# imxbblcd.net
KiCad netlist of a schematic drawn in Altium Designer
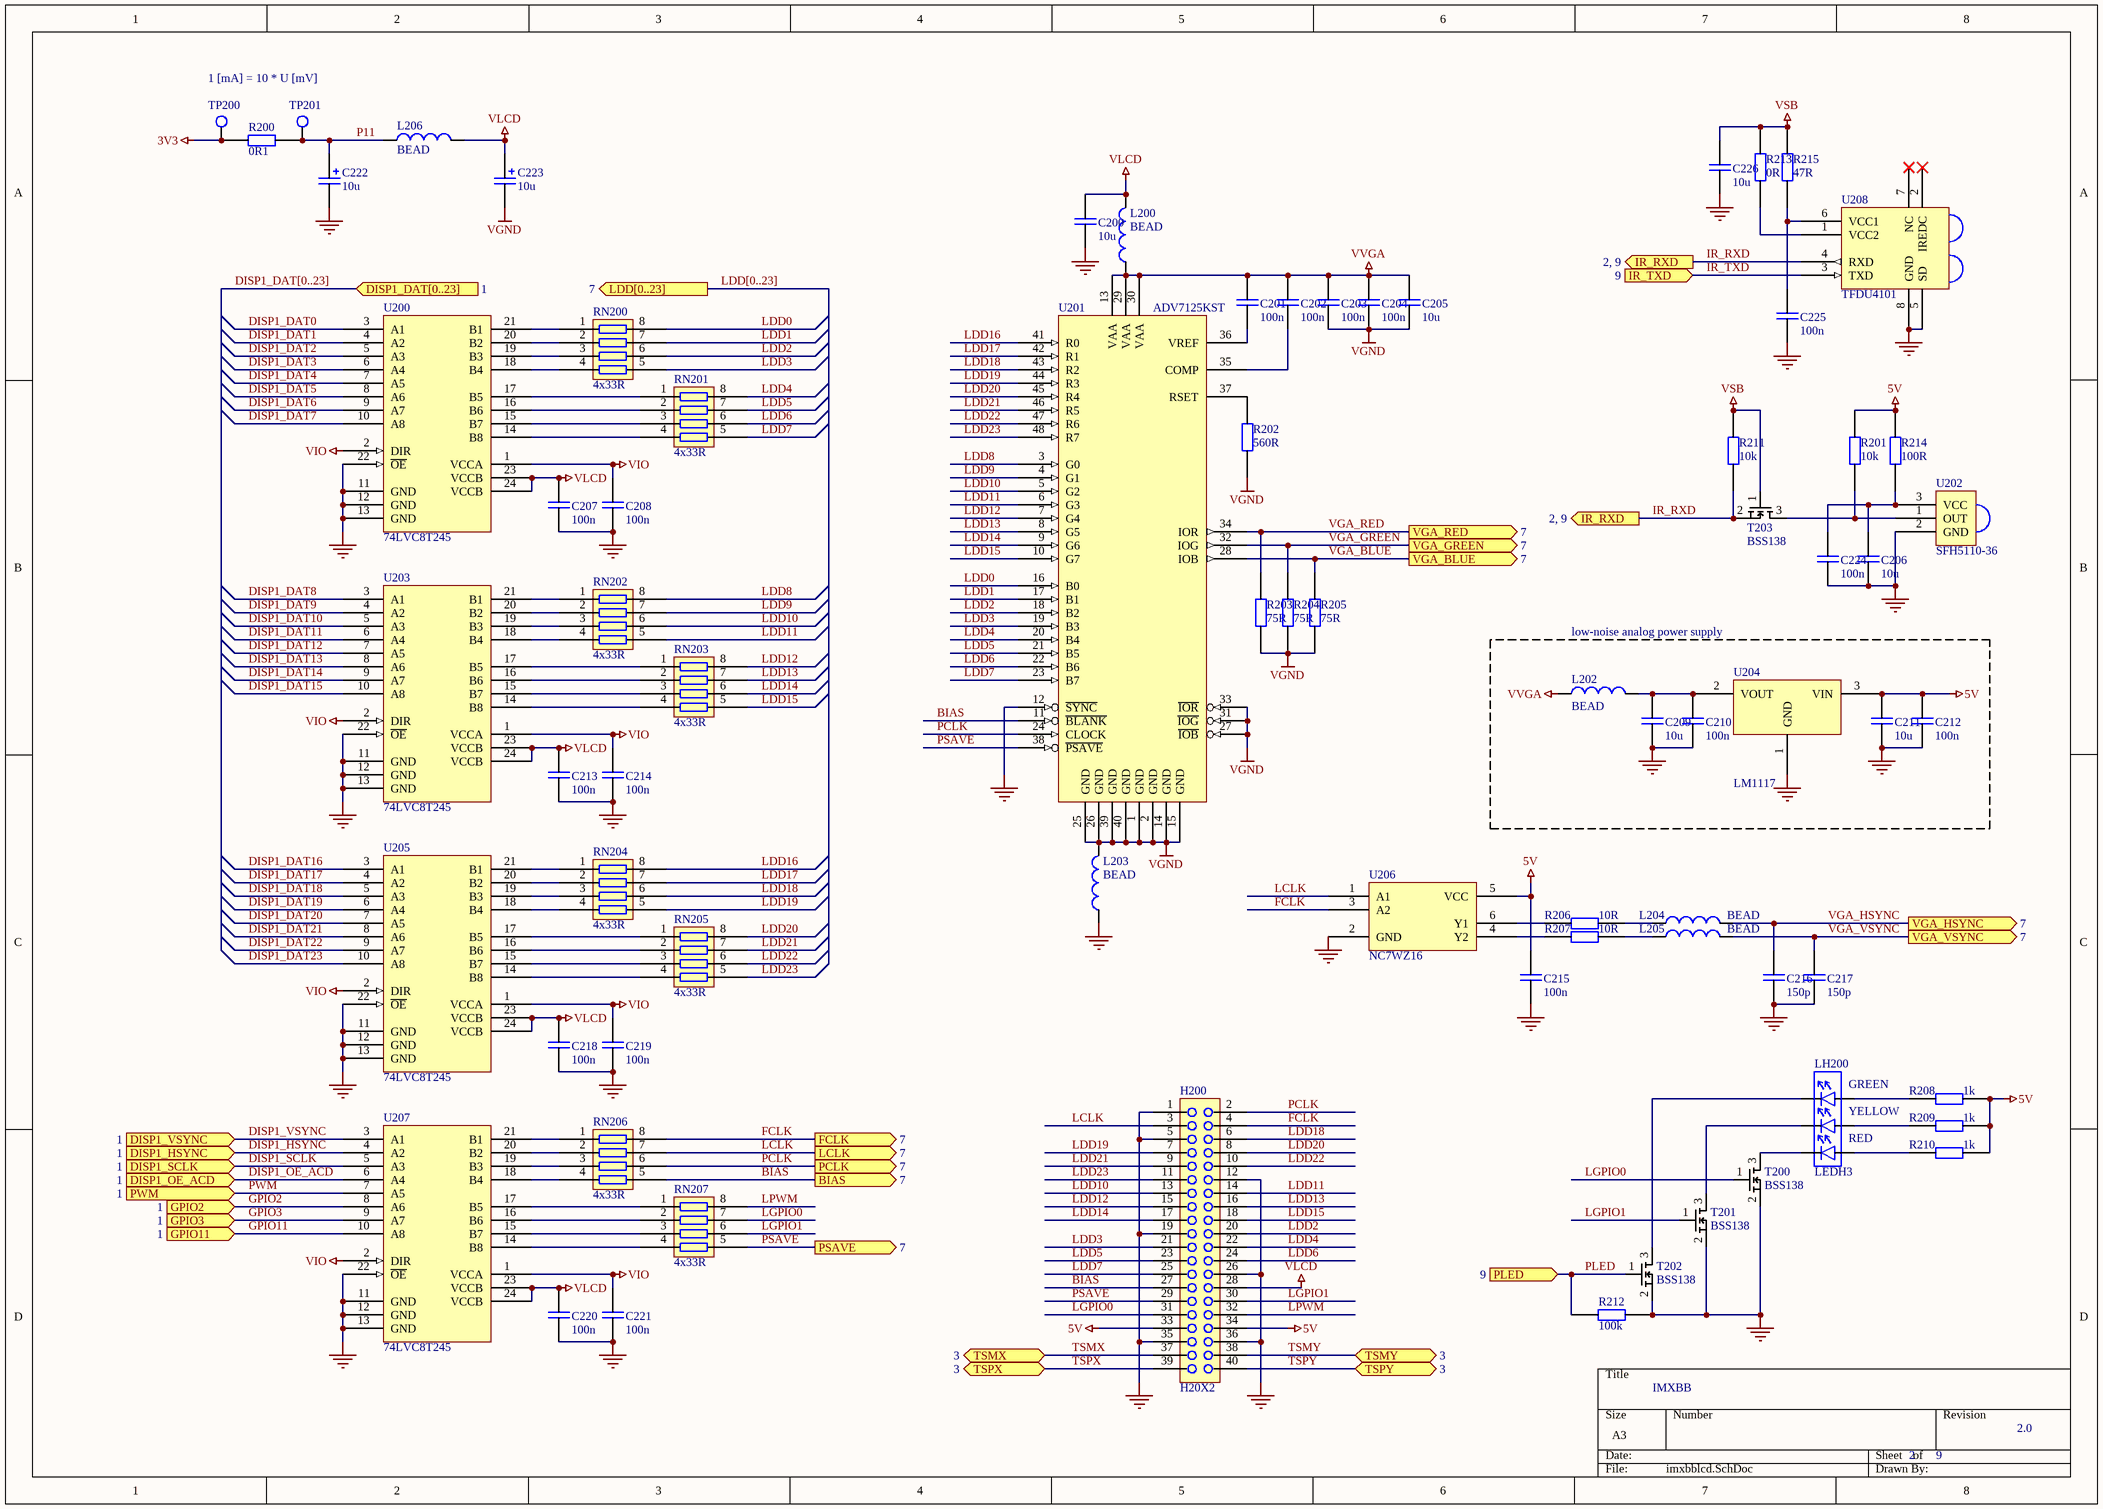
[diagram p0: imxbblcd.SchDoc]

(export (version "E")
  (design (tool "Eeschema 10.0.6"))
  (components
    (comp (ref "C200") (value "10u") (footprint "0805") (libsource (lib "imxbb") (part "C")))
    (comp (ref "C201") (value "100n") (footprint "0603") (libsource (lib "imxbb") (part "C")))
    (comp (ref "C202") (value "100n") (footprint "0603") (libsource (lib "imxbb") (part "C")))
    (comp (ref "C203") (value "100n") (footprint "0603") (libsource (lib "imxbb") (part "C")))
    (comp (ref "C204") (value "100n") (footprint "0603") (libsource (lib "imxbb") (part "C")))
    (comp (ref "C205") (value "10u") (footprint "0805") (libsource (lib "imxbb") (part "C")))
    (comp (ref "C206") (value "10u") (footprint "0805") (libsource (lib "imxbb") (part "C")))
    (comp (ref "C207") (value "100n") (footprint "0603") (libsource (lib "imxbb") (part "C")))
    (comp (ref "C208") (value "100n") (footprint "0603") (libsource (lib "imxbb") (part "C")))
    (comp (ref "C209") (value "10u") (footprint "0805") (libsource (lib "imxbb") (part "C")))
    (comp (ref "C210") (value "100n") (footprint "0603") (libsource (lib "imxbb") (part "C")))
    (comp (ref "C211") (value "10u") (footprint "0805") (libsource (lib "imxbb") (part "C")))
    (comp (ref "C212") (value "100n") (footprint "0603") (libsource (lib "imxbb") (part "C")))
    (comp (ref "C213") (value "100n") (footprint "0603") (libsource (lib "imxbb") (part "C")))
    (comp (ref "C214") (value "100n") (footprint "0603") (libsource (lib "imxbb") (part "C")))
    (comp (ref "C215") (value "100n") (footprint "0603") (libsource (lib "imxbb") (part "C")))
    (comp (ref "C216") (value "150p") (footprint "0603") (libsource (lib "imxbb") (part "C")))
    (comp (ref "C217") (value "150p") (footprint "0603") (libsource (lib "imxbb") (part "C")))
    (comp (ref "C218") (value "100n") (footprint "0603") (libsource (lib "imxbb") (part "C")))
    (comp (ref "C219") (value "100n") (footprint "0603") (libsource (lib "imxbb") (part "C")))
    (comp (ref "C220") (value "100n") (footprint "0603") (libsource (lib "imxbb") (part "C")))
    (comp (ref "C221") (value "100n") (footprint "0603") (libsource (lib "imxbb") (part "C")))
    (comp (ref "C222") (value "10u") (footprint "3216A") (libsource (lib "imxbb") (part "C+")))
    (comp (ref "C223") (value "10u") (footprint "3216A") (libsource (lib "imxbb") (part "C+")))
    (comp (ref "C224") (value "100n") (footprint "0603") (libsource (lib "imxbb") (part "C")))
    (comp (ref "C225") (value "100n") (footprint "0603") (libsource (lib "imxbb") (part "C")))
    (comp (ref "C226") (value "10u") (footprint "0805") (libsource (lib "imxbb") (part "C")))
    (comp (ref "H200") (value "H20X2") (footprint "H2x20") (libsource (lib "imxbb") (part "H20X2")))
    (comp (ref "L200") (value "BEAD") (footprint "0603") (libsource (lib "imxbb") (part "FBEAD")))
    (comp (ref "L202") (value "BEAD") (footprint "0603") (libsource (lib "imxbb") (part "FBEAD")))
    (comp (ref "L203") (value "BEAD") (footprint "0603") (libsource (lib "imxbb") (part "FBEAD")))
    (comp (ref "L204") (value "BEAD") (footprint "0603") (libsource (lib "imxbb") (part "FBEAD")))
    (comp (ref "L205") (value "BEAD") (footprint "0603") (libsource (lib "imxbb") (part "FBEAD")))
    (comp (ref "L206") (value "BEAD") (footprint "0603") (libsource (lib "") (part "FBEAD_1")))
    (comp (ref "LH200") (value "LEDH3") (footprint "LED HOLDER 3") (libsource (lib "imxbb") (part "LEDH3")))
    (comp (ref "R200") (value "0R1") (footprint "0603") (libsource (lib "") (part "R_3")))
    (comp (ref "R201") (value "10k") (footprint "0603") (libsource (lib "") (part "R_2")))
    (comp (ref "R202") (value "560R") (footprint "0603") (libsource (lib "") (part "R_1")))
    (comp (ref "R203") (value "75R") (footprint "0603") (libsource (lib "") (part "R_1")))
    (comp (ref "R204") (value "75R") (footprint "0603") (libsource (lib "") (part "R_1")))
    (comp (ref "R205") (value "75R") (footprint "0603") (libsource (lib "") (part "R_1")))
    (comp (ref "R206") (value "10R") (footprint "0603") (libsource (lib "imxbb") (part "R")))
    (comp (ref "R207") (value "10R") (footprint "0603") (libsource (lib "imxbb") (part "R")))
    (comp (ref "R208") (value "1k") (footprint "0603") (libsource (lib "imxbb") (part "R")))
    (comp (ref "R209") (value "1k") (footprint "0603") (libsource (lib "imxbb") (part "R")))
    (comp (ref "R210") (value "1k") (footprint "0603") (libsource (lib "imxbb") (part "R")))
    (comp (ref "R211") (value "10k") (footprint "0603") (libsource (lib "") (part "R_2")))
    (comp (ref "R212") (value "100k") (footprint "0603") (libsource (lib "") (part "R_3")))
    (comp (ref "R213") (value "0R") (footprint "0603") (libsource (lib "") (part "R_1")))
    (comp (ref "R214") (value "100R") (footprint "0603") (libsource (lib "") (part "R_2")))
    (comp (ref "R215") (value "47R") (footprint "0603") (libsource (lib "") (part "R_2")))
    (comp (ref "RN200") (value "4x33R") (footprint "RX4_NS") (libsource (lib "imxbb") (part "RN4")))
    (comp (ref "RN201") (value "4x33R") (footprint "RX4_NS") (libsource (lib "imxbb") (part "RN4")))
    (comp (ref "RN202") (value "4x33R") (footprint "RX4_NS") (libsource (lib "imxbb") (part "RN4")))
    (comp (ref "RN203") (value "4x33R") (footprint "RX4_NS") (libsource (lib "imxbb") (part "RN4")))
    (comp (ref "RN204") (value "4x33R") (footprint "RX4_NS") (libsource (lib "imxbb") (part "RN4")))
    (comp (ref "RN205") (value "4x33R") (footprint "RX4_NS") (libsource (lib "imxbb") (part "RN4")))
    (comp (ref "RN206") (value "4x33R") (footprint "RX4_NS") (libsource (lib "imxbb") (part "RN4")))
    (comp (ref "RN207") (value "4x33R") (footprint "RX4_NS") (libsource (lib "imxbb") (part "RN4")))
    (comp (ref "T200") (value "BSS138") (footprint "SOT23") (libsource (lib "imxbb") (part "BSS138")))
    (comp (ref "T201") (value "BSS138") (footprint "SOT23") (libsource (lib "imxbb") (part "BSS138")))
    (comp (ref "T202") (value "BSS138") (footprint "SOT23") (libsource (lib "imxbb") (part "BSS138")))
    (comp (ref "T203") (value "BSS138") (footprint "SOT23") (libsource (lib "imxbb") (part "BSS138")))
    (comp (ref "TP200")
      (value "TESTPOINT")
      (footprint "TESTPOINT_2mm")
      (description "Testpoint pad")
      (libsource (lib "imxbb") (part "TESTPOINT"))
    )
    (comp (ref "TP201")
      (value "TESTPOINT")
      (footprint "TESTPOINT_2mm")
      (description "Testpoint pad")
      (libsource (lib "imxbb") (part "TESTPOINT"))
    )
    (comp (ref "U200")
      (value "74LVC8T245")
      (footprint "TSSOP24")
      (libsource (lib "imxbb") (part "74LVC8T245"))
    )
    (comp (ref "U201") (value "ADV7125KST") (footprint "LQFP48") (libsource (lib "imxbb") (part "ADV7125")))
    (comp (ref "U202") (value "SFH5110-36") (footprint "SFH511x") (libsource (lib "imxbb") (part "SFH5110")))
    (comp (ref "U203")
      (value "74LVC8T245")
      (footprint "TSSOP24")
      (libsource (lib "imxbb") (part "74LVC8T245"))
    )
    (comp (ref "U204") (value "LM1117") (footprint "SOT223") (libsource (lib "imxbb") (part "LM1117")))
    (comp (ref "U205")
      (value "74LVC8T245")
      (footprint "TSSOP24")
      (libsource (lib "imxbb") (part "74LVC8T245"))
    )
    (comp (ref "U206") (value "NC7WZ16") (footprint "SC70") (libsource (lib "imxbb") (part "NC7WZ16")))
    (comp (ref "U207")
      (value "74LVC8T245")
      (footprint "TSSOP24")
      (libsource (lib "imxbb") (part "74LVC8T245"))
    )
    (comp (ref "U208") (value "TFDU4101") (footprint "TDFU4101") (libsource (lib "imxbb") (part "TFDU4101")))
  )
  (nets
    (net (code "1") (name "/BIAS") (class "Default")
      (node (ref "H200") (pin "27") (pinfunction "27_27") (pintype "passive"))
      (node (ref "RN206") (pin "5") (pintype "passive"))
      (node (ref "U201") (pin "11") (pinfunction "~{BLANK}_11") (pintype "input"))
    )
    (net (code "2") (name "/DISP1_DAT0") (class "Default")
      (node (ref "U200") (pin "3") (pinfunction "A1_3") (pintype "passive"))
    )
    (net (code "3") (name "/DISP1_DAT1") (class "Default")
      (node (ref "U200") (pin "4") (pinfunction "A2_4") (pintype "passive"))
    )
    (net (code "4") (name "/DISP1_DAT2") (class "Default")
      (node (ref "U200") (pin "5") (pinfunction "A3_5") (pintype "passive"))
    )
    (net (code "5") (name "/DISP1_DAT3") (class "Default")
      (node (ref "U200") (pin "6") (pinfunction "A4_6") (pintype "passive"))
    )
    (net (code "6") (name "/DISP1_DAT4") (class "Default")
      (node (ref "U200") (pin "7") (pinfunction "A5_7") (pintype "passive"))
    )
    (net (code "7") (name "/DISP1_DAT5") (class "Default")
      (node (ref "U200") (pin "8") (pinfunction "A6_8") (pintype "passive"))
    )
    (net (code "8") (name "/DISP1_DAT6") (class "Default")
      (node (ref "U200") (pin "9") (pinfunction "A7_9") (pintype "passive"))
    )
    (net (code "9") (name "/DISP1_DAT7") (class "Default")
      (node (ref "U200") (pin "10") (pinfunction "A8_10") (pintype "passive"))
    )
    (net (code "10") (name "/DISP1_DAT8") (class "Default")
      (node (ref "U203") (pin "3") (pinfunction "A1_3") (pintype "passive"))
    )
    (net (code "11") (name "/DISP1_DAT9") (class "Default")
      (node (ref "U203") (pin "4") (pinfunction "A2_4") (pintype "passive"))
    )
    (net (code "12") (name "/DISP1_DAT10") (class "Default")
      (node (ref "U203") (pin "5") (pinfunction "A3_5") (pintype "passive"))
    )
    (net (code "13") (name "/DISP1_DAT11") (class "Default")
      (node (ref "U203") (pin "6") (pinfunction "A4_6") (pintype "passive"))
    )
    (net (code "14") (name "/DISP1_DAT12") (class "Default")
      (node (ref "U203") (pin "7") (pinfunction "A5_7") (pintype "passive"))
    )
    (net (code "15") (name "/DISP1_DAT13") (class "Default")
      (node (ref "U203") (pin "8") (pinfunction "A6_8") (pintype "passive"))
    )
    (net (code "16") (name "/DISP1_DAT14") (class "Default")
      (node (ref "U203") (pin "9") (pinfunction "A7_9") (pintype "passive"))
    )
    (net (code "17") (name "/DISP1_DAT15") (class "Default")
      (node (ref "U203") (pin "10") (pinfunction "A8_10") (pintype "passive"))
    )
    (net (code "18") (name "/DISP1_DAT16") (class "Default")
      (node (ref "U205") (pin "3") (pinfunction "A1_3") (pintype "passive"))
    )
    (net (code "19") (name "/DISP1_DAT17") (class "Default")
      (node (ref "U205") (pin "4") (pinfunction "A2_4") (pintype "passive"))
    )
    (net (code "20") (name "/DISP1_DAT18") (class "Default")
      (node (ref "U205") (pin "5") (pinfunction "A3_5") (pintype "passive"))
    )
    (net (code "21") (name "/DISP1_DAT19") (class "Default")
      (node (ref "U205") (pin "6") (pinfunction "A4_6") (pintype "passive"))
    )
    (net (code "22") (name "/DISP1_DAT20") (class "Default")
      (node (ref "U205") (pin "7") (pinfunction "A5_7") (pintype "passive"))
    )
    (net (code "23") (name "/DISP1_DAT21") (class "Default")
      (node (ref "U205") (pin "8") (pinfunction "A6_8") (pintype "passive"))
    )
    (net (code "24") (name "/DISP1_DAT22") (class "Default")
      (node (ref "U205") (pin "9") (pinfunction "A7_9") (pintype "passive"))
    )
    (net (code "25") (name "/DISP1_DAT23") (class "Default")
      (node (ref "U205") (pin "10") (pinfunction "A8_10") (pintype "passive"))
    )
    (net (code "27") (name "/DISP1_HSYNC") (class "Default")
      (node (ref "U207") (pin "4") (pinfunction "A2_4") (pintype "passive"))
    )
    (net (code "28") (name "/DISP1_OE_ACD") (class "Default")
      (node (ref "U207") (pin "6") (pinfunction "A4_6") (pintype "passive"))
    )
    (net (code "29") (name "/DISP1_SCLK") (class "Default")
      (node (ref "U207") (pin "5") (pinfunction "A3_5") (pintype "passive"))
    )
    (net (code "30") (name "/DISP1_VSYNC") (class "Default")
      (node (ref "U207") (pin "3") (pinfunction "A1_3") (pintype "passive"))
    )
    (net (code "31") (name "/FCLK") (class "Default")
      (node (ref "H200") (pin "4") (pinfunction "4_4") (pintype "passive"))
      (node (ref "RN206") (pin "8") (pintype "passive"))
      (node (ref "U206") (pin "3") (pinfunction "A2_3") (pintype "passive"))
    )
    (net (code "32") (name "/GPIO2") (class "Default")
      (node (ref "U207") (pin "8") (pinfunction "A6_8") (pintype "passive"))
    )
    (net (code "33") (name "/GPIO3") (class "Default")
      (node (ref "U207") (pin "9") (pinfunction "A7_9") (pintype "passive"))
    )
    (net (code "34") (name "/GPIO11") (class "Default")
      (node (ref "U207") (pin "10") (pinfunction "A8_10") (pintype "passive"))
    )
    (net (code "35") (name "/IR_RXD") (class "Default")
      (node (ref "R211") (pin "2") (pinfunction "2_2") (pintype "passive"))
      (node (ref "T203") (pin "2") (pinfunction "S_2") (pintype "passive"))
      (node (ref "U208") (pin "4") (pinfunction "RXD_4") (pintype "output"))
    )
    (net (code "36") (name "/IR_TXD") (class "Default")
      (node (ref "U208") (pin "3") (pinfunction "TXD_3") (pintype "input"))
    )
    (net (code "37") (name "/LCLK") (class "Default")
      (node (ref "H200") (pin "3") (pinfunction "3_3") (pintype "passive"))
      (node (ref "RN206") (pin "7") (pintype "passive"))
      (node (ref "U206") (pin "1") (pinfunction "A1_1") (pintype "passive"))
    )
    (net (code "38") (name "/LDD0") (class "Default")
      (node (ref "RN200") (pin "8") (pintype "passive"))
      (node (ref "U201") (pin "16") (pinfunction "B0_16") (pintype "input"))
    )
    (net (code "39") (name "/LDD1") (class "Default")
      (node (ref "RN200") (pin "7") (pintype "passive"))
      (node (ref "U201") (pin "17") (pinfunction "B1_17") (pintype "input"))
    )
    (net (code "40") (name "/LDD2") (class "Default")
      (node (ref "H200") (pin "20") (pinfunction "20_20") (pintype "passive"))
      (node (ref "RN200") (pin "6") (pintype "passive"))
      (node (ref "U201") (pin "18") (pinfunction "B2_18") (pintype "input"))
    )
    (net (code "41") (name "/LDD3") (class "Default")
      (node (ref "H200") (pin "21") (pinfunction "21_21") (pintype "passive"))
      (node (ref "RN200") (pin "5") (pintype "passive"))
      (node (ref "U201") (pin "19") (pinfunction "B3_19") (pintype "input"))
    )
    (net (code "42") (name "/LDD4") (class "Default")
      (node (ref "H200") (pin "22") (pinfunction "22_22") (pintype "passive"))
      (node (ref "RN201") (pin "8") (pintype "passive"))
      (node (ref "U201") (pin "20") (pinfunction "B4_20") (pintype "input"))
    )
    (net (code "43") (name "/LDD5") (class "Default")
      (node (ref "H200") (pin "23") (pinfunction "23_23") (pintype "passive"))
      (node (ref "RN201") (pin "7") (pintype "passive"))
      (node (ref "U201") (pin "21") (pinfunction "B5_21") (pintype "input"))
    )
    (net (code "44") (name "/LDD6") (class "Default")
      (node (ref "H200") (pin "24") (pinfunction "24_24") (pintype "passive"))
      (node (ref "RN201") (pin "6") (pintype "passive"))
      (node (ref "U201") (pin "22") (pinfunction "B6_22") (pintype "input"))
    )
    (net (code "45") (name "/LDD7") (class "Default")
      (node (ref "H200") (pin "25") (pinfunction "25_25") (pintype "passive"))
      (node (ref "RN201") (pin "5") (pintype "passive"))
      (node (ref "U201") (pin "23") (pinfunction "B7_23") (pintype "input"))
    )
    (net (code "46") (name "/LDD8") (class "Default")
      (node (ref "RN202") (pin "8") (pintype "passive"))
      (node (ref "U201") (pin "3") (pinfunction "G0_3") (pintype "input"))
    )
    (net (code "47") (name "/LDD9") (class "Default")
      (node (ref "RN202") (pin "7") (pintype "passive"))
      (node (ref "U201") (pin "4") (pinfunction "G1_4") (pintype "input"))
    )
    (net (code "48") (name "/LDD10") (class "Default")
      (node (ref "H200") (pin "13") (pinfunction "13_13") (pintype "passive"))
      (node (ref "RN202") (pin "6") (pintype "passive"))
      (node (ref "U201") (pin "5") (pinfunction "G2_5") (pintype "input"))
    )
    (net (code "49") (name "/LDD11") (class "Default")
      (node (ref "H200") (pin "14") (pinfunction "14_14") (pintype "passive"))
      (node (ref "RN202") (pin "5") (pintype "passive"))
      (node (ref "U201") (pin "6") (pinfunction "G3_6") (pintype "input"))
    )
    (net (code "50") (name "/LDD12") (class "Default")
      (node (ref "H200") (pin "15") (pinfunction "15_15") (pintype "passive"))
      (node (ref "RN203") (pin "8") (pintype "passive"))
      (node (ref "U201") (pin "7") (pinfunction "G4_7") (pintype "input"))
    )
    (net (code "51") (name "/LDD13") (class "Default")
      (node (ref "H200") (pin "16") (pinfunction "16_16") (pintype "passive"))
      (node (ref "RN203") (pin "7") (pintype "passive"))
      (node (ref "U201") (pin "8") (pinfunction "G5_8") (pintype "input"))
    )
    (net (code "52") (name "/LDD14") (class "Default")
      (node (ref "H200") (pin "17") (pinfunction "17_17") (pintype "passive"))
      (node (ref "RN203") (pin "6") (pintype "passive"))
      (node (ref "U201") (pin "9") (pinfunction "G6_9") (pintype "input"))
    )
    (net (code "53") (name "/LDD15") (class "Default")
      (node (ref "H200") (pin "18") (pinfunction "18_18") (pintype "passive"))
      (node (ref "RN203") (pin "5") (pintype "passive"))
      (node (ref "U201") (pin "10") (pinfunction "G7_10") (pintype "input"))
    )
    (net (code "54") (name "/LDD16") (class "Default")
      (node (ref "RN204") (pin "8") (pintype "passive"))
      (node (ref "U201") (pin "41") (pinfunction "R0_41") (pintype "input"))
    )
    (net (code "55") (name "/LDD17") (class "Default")
      (node (ref "RN204") (pin "7") (pintype "passive"))
      (node (ref "U201") (pin "42") (pinfunction "R1_42") (pintype "input"))
    )
    (net (code "56") (name "/LDD18") (class "Default")
      (node (ref "H200") (pin "6") (pinfunction "6_6") (pintype "passive"))
      (node (ref "RN204") (pin "6") (pintype "passive"))
      (node (ref "U201") (pin "43") (pinfunction "R2_43") (pintype "input"))
    )
    (net (code "57") (name "/LDD19") (class "Default")
      (node (ref "H200") (pin "7") (pinfunction "7_7") (pintype "passive"))
      (node (ref "RN204") (pin "5") (pintype "passive"))
      (node (ref "U201") (pin "44") (pinfunction "R3_44") (pintype "input"))
    )
    (net (code "58") (name "/LDD20") (class "Default")
      (node (ref "H200") (pin "8") (pinfunction "8_8") (pintype "passive"))
      (node (ref "RN205") (pin "8") (pintype "passive"))
      (node (ref "U201") (pin "45") (pinfunction "R4_45") (pintype "input"))
    )
    (net (code "59") (name "/LDD21") (class "Default")
      (node (ref "H200") (pin "9") (pinfunction "9_9") (pintype "passive"))
      (node (ref "RN205") (pin "7") (pintype "passive"))
      (node (ref "U201") (pin "46") (pinfunction "R5_46") (pintype "input"))
    )
    (net (code "60") (name "/LDD22") (class "Default")
      (node (ref "H200") (pin "10") (pinfunction "10_10") (pintype "passive"))
      (node (ref "RN205") (pin "6") (pintype "passive"))
      (node (ref "U201") (pin "47") (pinfunction "R6_47") (pintype "input"))
    )
    (net (code "61") (name "/LDD23") (class "Default")
      (node (ref "H200") (pin "11") (pinfunction "11_11") (pintype "passive"))
      (node (ref "RN205") (pin "5") (pintype "passive"))
      (node (ref "U201") (pin "48") (pinfunction "R7_48") (pintype "input"))
    )
    (net (code "63") (name "/LGPIO0") (class "Default")
      (node (ref "H200") (pin "31") (pinfunction "31_31") (pintype "passive"))
      (node (ref "RN207") (pin "7") (pintype "passive"))
      (node (ref "T200") (pin "1") (pinfunction "G_1") (pintype "passive"))
    )
    (net (code "64") (name "/LGPIO1") (class "Default")
      (node (ref "H200") (pin "30") (pinfunction "30_30") (pintype "passive"))
      (node (ref "RN207") (pin "6") (pintype "passive"))
      (node (ref "T201") (pin "1") (pinfunction "G_1") (pintype "passive"))
    )
    (net (code "65") (name "/LPWM") (class "Default")
      (node (ref "H200") (pin "32") (pinfunction "32_32") (pintype "passive"))
      (node (ref "RN207") (pin "8") (pintype "passive"))
    )
    (net (code "66") (name "/P11") (class "Default")
      (node (ref "C222") (pin "1") (pinfunction "1_1") (pintype "passive"))
      (node (ref "L206") (pin "2") (pinfunction "2_2") (pintype "passive"))
      (node (ref "R200") (pin "2") (pinfunction "2_2") (pintype "passive"))
      (node (ref "TP201") (pin "1") (pinfunction "1_1") (pintype "passive"))
    )
    (net (code "67") (name "/PCLK") (class "Default")
      (node (ref "H200") (pin "2") (pinfunction "2_2") (pintype "passive"))
      (node (ref "RN206") (pin "6") (pintype "passive"))
      (node (ref "U201") (pin "24") (pinfunction "CLOCK_24") (pintype "input"))
    )
    (net (code "68") (name "/PLED") (class "Default")
      (node (ref "R212") (pin "1") (pinfunction "1_1") (pintype "passive"))
      (node (ref "T202") (pin "1") (pinfunction "G_1") (pintype "passive"))
    )
    (net (code "69") (name "/PSAVE") (class "Default")
      (node (ref "H200") (pin "29") (pinfunction "29_29") (pintype "passive"))
      (node (ref "RN207") (pin "5") (pintype "passive"))
      (node (ref "U201") (pin "38") (pinfunction "~{PSAVE}_38") (pintype "input"))
    )
    (net (code "70") (name "/PWM") (class "Default")
      (node (ref "U207") (pin "7") (pinfunction "A5_7") (pintype "passive"))
    )
    (net (code "71") (name "/TSMX") (class "Default")
      (node (ref "H200") (pin "37") (pinfunction "37_37") (pintype "passive"))
    )
    (net (code "72") (name "/TSMY") (class "Default")
      (node (ref "H200") (pin "38") (pinfunction "38_38") (pintype "passive"))
    )
    (net (code "73") (name "/TSPX") (class "Default")
      (node (ref "H200") (pin "39") (pinfunction "39_39") (pintype "passive"))
    )
    (net (code "74") (name "/TSPY") (class "Default")
      (node (ref "H200") (pin "40") (pinfunction "40_40") (pintype "passive"))
    )
    (net (code "75") (name "/VGA_BLUE") (class "Default")
      (node (ref "R205") (pin "2") (pinfunction "2_2") (pintype "passive"))
      (node (ref "U201") (pin "28") (pinfunction "IOB_28") (pintype "output"))
    )
    (net (code "76") (name "/VGA_GREEN") (class "Default")
      (node (ref "R204") (pin "2") (pinfunction "2_2") (pintype "passive"))
      (node (ref "U201") (pin "32") (pinfunction "IOG_32") (pintype "output"))
    )
    (net (code "77") (name "/VGA_HSYNC") (class "Default")
      (node (ref "C216") (pin "2") (pinfunction "2_2") (pintype "passive"))
      (node (ref "L204") (pin "2") (pinfunction "2_2") (pintype "passive"))
    )
    (net (code "78") (name "/VGA_RED") (class "Default")
      (node (ref "R203") (pin "2") (pinfunction "2_2") (pintype "passive"))
      (node (ref "U201") (pin "34") (pinfunction "IOR_34") (pintype "output"))
    )
    (net (code "79") (name "/VGA_VSYNC") (class "Default")
      (node (ref "C217") (pin "2") (pinfunction "2_2") (pintype "passive"))
      (node (ref "L205") (pin "2") (pinfunction "2_2") (pintype "passive"))
    )
    (net (code "80") (name "3V3") (class "Default")
      (node (ref "R200") (pin "1") (pinfunction "1_1") (pintype "passive"))
      (node (ref "TP200") (pin "1") (pinfunction "1_1") (pintype "passive"))
    )
    (net (code "81") (name "5V") (class "Default")
      (node (ref "C211") (pin "2") (pinfunction "2_2") (pintype "passive"))
      (node (ref "C212") (pin "2") (pinfunction "2_2") (pintype "passive"))
      (node (ref "C215") (pin "2") (pinfunction "2_2") (pintype "passive"))
      (node (ref "H200") (pin "33") (pinfunction "33_33") (pintype "passive"))
      (node (ref "H200") (pin "34") (pinfunction "34_34") (pintype "passive"))
      (node (ref "R201") (pin "1") (pinfunction "1_1") (pintype "passive"))
      (node (ref "R208") (pin "1") (pinfunction "1_1") (pintype "passive"))
      (node (ref "R209") (pin "1") (pinfunction "1_1") (pintype "passive"))
      (node (ref "R210") (pin "1") (pinfunction "1_1") (pintype "passive"))
      (node (ref "R214") (pin "1") (pinfunction "1_1") (pintype "passive"))
      (node (ref "U204") (pin "3") (pinfunction "VIN_3") (pintype "passive"))
      (node (ref "U206") (pin "5") (pinfunction "VCC_5") (pintype "passive"))
    )
    (net (code "82") (name "GND") (class "Default")
      (node (ref "C200") (pin "1") (pinfunction "1_1") (pintype "passive"))
      (node (ref "C206") (pin "1") (pinfunction "1_1") (pintype "passive"))
      (node (ref "C207") (pin "1") (pinfunction "1_1") (pintype "passive"))
      (node (ref "C208") (pin "1") (pinfunction "1_1") (pintype "passive"))
      (node (ref "C209") (pin "1") (pinfunction "1_1") (pintype "passive"))
      (node (ref "C210") (pin "1") (pinfunction "1_1") (pintype "passive"))
      (node (ref "C211") (pin "1") (pinfunction "1_1") (pintype "passive"))
      (node (ref "C212") (pin "1") (pinfunction "1_1") (pintype "passive"))
      (node (ref "C213") (pin "1") (pinfunction "1_1") (pintype "passive"))
      (node (ref "C214") (pin "1") (pinfunction "1_1") (pintype "passive"))
      (node (ref "C215") (pin "1") (pinfunction "1_1") (pintype "passive"))
      (node (ref "C216") (pin "1") (pinfunction "1_1") (pintype "passive"))
      (node (ref "C217") (pin "1") (pinfunction "1_1") (pintype "passive"))
      (node (ref "C218") (pin "1") (pinfunction "1_1") (pintype "passive"))
      (node (ref "C219") (pin "1") (pinfunction "1_1") (pintype "passive"))
      (node (ref "C220") (pin "1") (pinfunction "1_1") (pintype "passive"))
      (node (ref "C221") (pin "1") (pinfunction "1_1") (pintype "passive"))
      (node (ref "C222") (pin "2") (pinfunction "2_2") (pintype "passive"))
      (node (ref "C224") (pin "1") (pinfunction "1_1") (pintype "passive"))
      (node (ref "C225") (pin "1") (pinfunction "1_1") (pintype "passive"))
      (node (ref "C226") (pin "1") (pinfunction "1_1") (pintype "passive"))
      (node (ref "H200") (pin "1") (pinfunction "1_1") (pintype "passive"))
      (node (ref "H200") (pin "12") (pinfunction "12_12") (pintype "passive"))
      (node (ref "H200") (pin "19") (pinfunction "19_19") (pintype "passive"))
      (node (ref "H200") (pin "26") (pinfunction "26_26") (pintype "passive"))
      (node (ref "H200") (pin "35") (pinfunction "35_35") (pintype "passive"))
      (node (ref "H200") (pin "36") (pinfunction "36_36") (pintype "passive"))
      (node (ref "H200") (pin "5") (pinfunction "5_5") (pintype "passive"))
      (node (ref "L203") (pin "1") (pinfunction "1_1") (pintype "passive"))
      (node (ref "R212") (pin "2") (pinfunction "2_2") (pintype "passive"))
      (node (ref "T200") (pin "2") (pinfunction "S_2") (pintype "passive"))
      (node (ref "T201") (pin "2") (pinfunction "S_2") (pintype "passive"))
      (node (ref "T202") (pin "2") (pinfunction "S_2") (pintype "passive"))
      (node (ref "U200") (pin "11") (pinfunction "GND_11") (pintype "power_in"))
      (node (ref "U200") (pin "12") (pinfunction "GND_12") (pintype "power_in"))
      (node (ref "U200") (pin "13") (pinfunction "GND_13") (pintype "power_in"))
      (node (ref "U200") (pin "22") (pinfunction "~{OE}_22") (pintype "input"))
      (node (ref "U201") (pin "12") (pinfunction "~{SYNC}_12") (pintype "input"))
      (node (ref "U202") (pin "2") (pinfunction "GND_2") (pintype "passive"))
      (node (ref "U203") (pin "11") (pinfunction "GND_11") (pintype "power_in"))
      (node (ref "U203") (pin "12") (pinfunction "GND_12") (pintype "power_in"))
      (node (ref "U203") (pin "13") (pinfunction "GND_13") (pintype "power_in"))
      (node (ref "U203") (pin "22") (pinfunction "~{OE}_22") (pintype "input"))
      (node (ref "U204") (pin "1") (pinfunction "GND_1") (pintype "passive"))
      (node (ref "U205") (pin "11") (pinfunction "GND_11") (pintype "power_in"))
      (node (ref "U205") (pin "12") (pinfunction "GND_12") (pintype "power_in"))
      (node (ref "U205") (pin "13") (pinfunction "GND_13") (pintype "power_in"))
      (node (ref "U205") (pin "22") (pinfunction "~{OE}_22") (pintype "input"))
      (node (ref "U206") (pin "2") (pinfunction "GND_2") (pintype "passive"))
      (node (ref "U207") (pin "11") (pinfunction "GND_11") (pintype "power_in"))
      (node (ref "U207") (pin "12") (pinfunction "GND_12") (pintype "power_in"))
      (node (ref "U207") (pin "13") (pinfunction "GND_13") (pintype "power_in"))
      (node (ref "U207") (pin "22") (pinfunction "~{OE}_22") (pintype "input"))
      (node (ref "U208") (pin "5") (pinfunction "SD_5") (pintype "passive"))
      (node (ref "U208") (pin "8") (pinfunction "GND_8") (pintype "passive"))
    )
    (net (code "83") (name "Net-(L204-Pad1)") (class "Default")
      (node (ref "L204") (pin "1") (pinfunction "1_1") (pintype "passive"))
      (node (ref "R206") (pin "1") (pinfunction "1_1") (pintype "passive"))
    )
    (net (code "84") (name "Net-(L205-Pad1)") (class "Default")
      (node (ref "L205") (pin "1") (pinfunction "1_1") (pintype "passive"))
      (node (ref "R207") (pin "1") (pinfunction "1_1") (pintype "passive"))
    )
    (net (code "85") (name "Net-(LH200-Pad2)") (class "Default")
      (node (ref "LH200") (pin "2") (pinfunction "2_2") (pintype "passive"))
      (node (ref "R208") (pin "2") (pinfunction "2_2") (pintype "passive"))
    )
    (net (code "86") (name "Net-(LH200-Pad4)") (class "Default")
      (node (ref "LH200") (pin "4") (pinfunction "4_4") (pintype "passive"))
      (node (ref "R209") (pin "2") (pinfunction "2_2") (pintype "passive"))
    )
    (net (code "87") (name "Net-(LH200-Pad6)") (class "Default")
      (node (ref "LH200") (pin "6") (pinfunction "6_6") (pintype "passive"))
      (node (ref "R210") (pin "2") (pinfunction "2_2") (pintype "passive"))
    )
    (net (code "88") (name "Net-(T200-D)") (class "Default")
      (node (ref "LH200") (pin "5") (pinfunction "5_5") (pintype "passive"))
      (node (ref "T200") (pin "3") (pinfunction "D_3") (pintype "passive"))
    )
    (net (code "89") (name "Net-(T201-D)") (class "Default")
      (node (ref "LH200") (pin "3") (pinfunction "3_3") (pintype "passive"))
      (node (ref "T201") (pin "3") (pinfunction "D_3") (pintype "passive"))
    )
    (net (code "90") (name "Net-(T202-D)") (class "Default")
      (node (ref "LH200") (pin "1") (pinfunction "1_1") (pintype "passive"))
      (node (ref "T202") (pin "3") (pinfunction "D_3") (pintype "passive"))
    )
    (net (code "91") (name "Net-(T203-D)") (class "Default")
      (node (ref "R201") (pin "2") (pinfunction "2_2") (pintype "passive"))
      (node (ref "T203") (pin "3") (pinfunction "D_3") (pintype "passive"))
      (node (ref "U202") (pin "1") (pinfunction "OUT_1") (pintype "passive"))
    )
    (net (code "92") (name "Net-(U200-B1)") (class "Default")
      (node (ref "RN200") (pin "1") (pintype "passive"))
      (node (ref "U200") (pin "21") (pinfunction "B1_21") (pintype "passive"))
    )
    (net (code "93") (name "Net-(U200-B2)") (class "Default")
      (node (ref "RN200") (pin "2") (pintype "passive"))
      (node (ref "U200") (pin "20") (pinfunction "B2_20") (pintype "passive"))
    )
    (net (code "94") (name "Net-(U200-B3)") (class "Default")
      (node (ref "RN200") (pin "3") (pintype "passive"))
      (node (ref "U200") (pin "19") (pinfunction "B3_19") (pintype "passive"))
    )
    (net (code "95") (name "Net-(U200-B4)") (class "Default")
      (node (ref "RN200") (pin "4") (pintype "passive"))
      (node (ref "U200") (pin "18") (pinfunction "B4_18") (pintype "passive"))
    )
    (net (code "96") (name "Net-(U200-B5)") (class "Default")
      (node (ref "RN201") (pin "1") (pintype "passive"))
      (node (ref "U200") (pin "17") (pinfunction "B5_17") (pintype "passive"))
    )
    (net (code "97") (name "Net-(U200-B6)") (class "Default")
      (node (ref "RN201") (pin "2") (pintype "passive"))
      (node (ref "U200") (pin "16") (pinfunction "B6_16") (pintype "passive"))
    )
    (net (code "98") (name "Net-(U200-B7)") (class "Default")
      (node (ref "RN201") (pin "3") (pintype "passive"))
      (node (ref "U200") (pin "15") (pinfunction "B7_15") (pintype "passive"))
    )
    (net (code "99") (name "Net-(U200-B8)") (class "Default")
      (node (ref "RN201") (pin "4") (pintype "passive"))
      (node (ref "U200") (pin "14") (pinfunction "B8_14") (pintype "passive"))
    )
    (net (code "100") (name "Net-(U201-COMP)") (class "Default")
      (node (ref "C202") (pin "1") (pinfunction "1_1") (pintype "passive"))
      (node (ref "U201") (pin "35") (pinfunction "COMP_35") (pintype "passive"))
    )
    (net (code "101") (name "Net-(U201-RSET)") (class "Default")
      (node (ref "R202") (pin "2") (pinfunction "2_2") (pintype "passive"))
      (node (ref "U201") (pin "37") (pinfunction "RSET_37") (pintype "passive"))
    )
    (net (code "102") (name "Net-(U201-VREF)") (class "Default")
      (node (ref "C201") (pin "1") (pinfunction "1_1") (pintype "passive"))
      (node (ref "U201") (pin "36") (pinfunction "VREF_36") (pintype "passive"))
    )
    (net (code "103") (name "Net-(U202-VCC)") (class "Default")
      (node (ref "C206") (pin "2") (pinfunction "2_2") (pintype "passive"))
      (node (ref "C224") (pin "2") (pinfunction "2_2") (pintype "passive"))
      (node (ref "R214") (pin "2") (pinfunction "2_2") (pintype "passive"))
      (node (ref "U202") (pin "3") (pinfunction "VCC_3") (pintype "passive"))
    )
    (net (code "104") (name "Net-(U203-B1)") (class "Default")
      (node (ref "RN202") (pin "1") (pintype "passive"))
      (node (ref "U203") (pin "21") (pinfunction "B1_21") (pintype "passive"))
    )
    (net (code "105") (name "Net-(U203-B2)") (class "Default")
      (node (ref "RN202") (pin "2") (pintype "passive"))
      (node (ref "U203") (pin "20") (pinfunction "B2_20") (pintype "passive"))
    )
    (net (code "106") (name "Net-(U203-B3)") (class "Default")
      (node (ref "RN202") (pin "3") (pintype "passive"))
      (node (ref "U203") (pin "19") (pinfunction "B3_19") (pintype "passive"))
    )
    (net (code "107") (name "Net-(U203-B4)") (class "Default")
      (node (ref "RN202") (pin "4") (pintype "passive"))
      (node (ref "U203") (pin "18") (pinfunction "B4_18") (pintype "passive"))
    )
    (net (code "108") (name "Net-(U203-B5)") (class "Default")
      (node (ref "RN203") (pin "1") (pintype "passive"))
      (node (ref "U203") (pin "17") (pinfunction "B5_17") (pintype "passive"))
    )
    (net (code "109") (name "Net-(U203-B6)") (class "Default")
      (node (ref "RN203") (pin "2") (pintype "passive"))
      (node (ref "U203") (pin "16") (pinfunction "B6_16") (pintype "passive"))
    )
    (net (code "110") (name "Net-(U203-B7)") (class "Default")
      (node (ref "RN203") (pin "3") (pintype "passive"))
      (node (ref "U203") (pin "15") (pinfunction "B7_15") (pintype "passive"))
    )
    (net (code "111") (name "Net-(U203-B8)") (class "Default")
      (node (ref "RN203") (pin "4") (pintype "passive"))
      (node (ref "U203") (pin "14") (pinfunction "B8_14") (pintype "passive"))
    )
    (net (code "112") (name "Net-(U204-VOUT)") (class "Default")
      (node (ref "C209") (pin "2") (pinfunction "2_2") (pintype "passive"))
      (node (ref "C210") (pin "2") (pinfunction "2_2") (pintype "passive"))
      (node (ref "L202") (pin "2") (pinfunction "2_2") (pintype "passive"))
      (node (ref "U204") (pin "2") (pinfunction "VOUT_2") (pintype "passive"))
    )
    (net (code "113") (name "Net-(U205-B1)") (class "Default")
      (node (ref "RN204") (pin "1") (pintype "passive"))
      (node (ref "U205") (pin "21") (pinfunction "B1_21") (pintype "passive"))
    )
    (net (code "114") (name "Net-(U205-B2)") (class "Default")
      (node (ref "RN204") (pin "2") (pintype "passive"))
      (node (ref "U205") (pin "20") (pinfunction "B2_20") (pintype "passive"))
    )
    (net (code "115") (name "Net-(U205-B3)") (class "Default")
      (node (ref "RN204") (pin "3") (pintype "passive"))
      (node (ref "U205") (pin "19") (pinfunction "B3_19") (pintype "passive"))
    )
    (net (code "116") (name "Net-(U205-B4)") (class "Default")
      (node (ref "RN204") (pin "4") (pintype "passive"))
      (node (ref "U205") (pin "18") (pinfunction "B4_18") (pintype "passive"))
    )
    (net (code "117") (name "Net-(U205-B5)") (class "Default")
      (node (ref "RN205") (pin "1") (pintype "passive"))
      (node (ref "U205") (pin "17") (pinfunction "B5_17") (pintype "passive"))
    )
    (net (code "118") (name "Net-(U205-B6)") (class "Default")
      (node (ref "RN205") (pin "2") (pintype "passive"))
      (node (ref "U205") (pin "16") (pinfunction "B6_16") (pintype "passive"))
    )
    (net (code "119") (name "Net-(U205-B7)") (class "Default")
      (node (ref "RN205") (pin "3") (pintype "passive"))
      (node (ref "U205") (pin "15") (pinfunction "B7_15") (pintype "passive"))
    )
    (net (code "120") (name "Net-(U205-B8)") (class "Default")
      (node (ref "RN205") (pin "4") (pintype "passive"))
      (node (ref "U205") (pin "14") (pinfunction "B8_14") (pintype "passive"))
    )
    (net (code "121") (name "Net-(U206-Y1)") (class "Default")
      (node (ref "R206") (pin "2") (pinfunction "2_2") (pintype "passive"))
      (node (ref "U206") (pin "6") (pinfunction "Y1_6") (pintype "passive"))
    )
    (net (code "122") (name "Net-(U206-Y2)") (class "Default")
      (node (ref "R207") (pin "2") (pinfunction "2_2") (pintype "passive"))
      (node (ref "U206") (pin "4") (pinfunction "Y2_4") (pintype "passive"))
    )
    (net (code "123") (name "Net-(U207-B1)") (class "Default")
      (node (ref "RN206") (pin "1") (pintype "passive"))
      (node (ref "U207") (pin "21") (pinfunction "B1_21") (pintype "passive"))
    )
    (net (code "124") (name "Net-(U207-B2)") (class "Default")
      (node (ref "RN206") (pin "2") (pintype "passive"))
      (node (ref "U207") (pin "20") (pinfunction "B2_20") (pintype "passive"))
    )
    (net (code "125") (name "Net-(U207-B3)") (class "Default")
      (node (ref "RN206") (pin "3") (pintype "passive"))
      (node (ref "U207") (pin "19") (pinfunction "B3_19") (pintype "passive"))
    )
    (net (code "126") (name "Net-(U207-B4)") (class "Default")
      (node (ref "RN206") (pin "4") (pintype "passive"))
      (node (ref "U207") (pin "18") (pinfunction "B4_18") (pintype "passive"))
    )
    (net (code "127") (name "Net-(U207-B5)") (class "Default")
      (node (ref "RN207") (pin "1") (pintype "passive"))
      (node (ref "U207") (pin "17") (pinfunction "B5_17") (pintype "passive"))
    )
    (net (code "128") (name "Net-(U207-B6)") (class "Default")
      (node (ref "RN207") (pin "2") (pintype "passive"))
      (node (ref "U207") (pin "16") (pinfunction "B6_16") (pintype "passive"))
    )
    (net (code "129") (name "Net-(U207-B7)") (class "Default")
      (node (ref "RN207") (pin "3") (pintype "passive"))
      (node (ref "U207") (pin "15") (pinfunction "B7_15") (pintype "passive"))
    )
    (net (code "130") (name "Net-(U207-B8)") (class "Default")
      (node (ref "RN207") (pin "4") (pintype "passive"))
      (node (ref "U207") (pin "14") (pinfunction "B8_14") (pintype "passive"))
    )
    (net (code "131") (name "Net-(U208-VCC1)") (class "Default")
      (node (ref "C225") (pin "2") (pinfunction "2_2") (pintype "passive"))
      (node (ref "R215") (pin "2") (pinfunction "2_2") (pintype "passive"))
      (node (ref "U208") (pin "6") (pinfunction "VCC1_6") (pintype "passive"))
    )
    (net (code "132") (name "Net-(U208-VCC2)") (class "Default")
      (node (ref "R213") (pin "1") (pinfunction "1_1") (pintype "passive"))
      (node (ref "U208") (pin "1") (pinfunction "VCC2_1") (pintype "passive"))
    )
    (net (code "133") (name "VGND") (class "Default")
      (node (ref "C203") (pin "1") (pinfunction "1_1") (pintype "passive"))
      (node (ref "C204") (pin "1") (pinfunction "1_1") (pintype "passive"))
      (node (ref "C205") (pin "1") (pinfunction "1_1") (pintype "passive"))
      (node (ref "C223") (pin "2") (pinfunction "2_2") (pintype "passive"))
      (node (ref "L203") (pin "2") (pinfunction "2_2") (pintype "passive"))
      (node (ref "R202") (pin "1") (pinfunction "1_1") (pintype "passive"))
      (node (ref "R203") (pin "1") (pinfunction "1_1") (pintype "passive"))
      (node (ref "R204") (pin "1") (pinfunction "1_1") (pintype "passive"))
      (node (ref "R205") (pin "1") (pinfunction "1_1") (pintype "passive"))
      (node (ref "U201") (pin "1") (pinfunction "GND_1") (pintype "power_in"))
      (node (ref "U201") (pin "14") (pinfunction "GND_14") (pintype "power_in"))
      (node (ref "U201") (pin "15") (pinfunction "GND_15") (pintype "power_in"))
      (node (ref "U201") (pin "2") (pinfunction "GND_2") (pintype "power_in"))
      (node (ref "U201") (pin "25") (pinfunction "GND_25") (pintype "power_in"))
      (node (ref "U201") (pin "26") (pinfunction "GND_26") (pintype "power_in"))
      (node (ref "U201") (pin "27") (pinfunction "~{IOB}_27") (pintype "input"))
      (node (ref "U201") (pin "31") (pinfunction "~{IOG}_31") (pintype "input"))
      (node (ref "U201") (pin "33") (pinfunction "~{IOR}_33") (pintype "input"))
      (node (ref "U201") (pin "39") (pinfunction "GND_39") (pintype "power_in"))
      (node (ref "U201") (pin "40") (pinfunction "GND_40") (pintype "power_in"))
    )
    (net (code "134") (name "VIO") (class "Default")
      (node (ref "C208") (pin "2") (pinfunction "2_2") (pintype "passive"))
      (node (ref "C214") (pin "2") (pinfunction "2_2") (pintype "passive"))
      (node (ref "C219") (pin "2") (pinfunction "2_2") (pintype "passive"))
      (node (ref "C221") (pin "2") (pinfunction "2_2") (pintype "passive"))
      (node (ref "U200") (pin "1") (pinfunction "VCCA_1") (pintype "power_in"))
      (node (ref "U200") (pin "2") (pinfunction "DIR_2") (pintype "input"))
      (node (ref "U203") (pin "1") (pinfunction "VCCA_1") (pintype "power_in"))
      (node (ref "U203") (pin "2") (pinfunction "DIR_2") (pintype "input"))
      (node (ref "U205") (pin "1") (pinfunction "VCCA_1") (pintype "power_in"))
      (node (ref "U205") (pin "2") (pinfunction "DIR_2") (pintype "input"))
      (node (ref "U207") (pin "1") (pinfunction "VCCA_1") (pintype "power_in"))
      (node (ref "U207") (pin "2") (pinfunction "DIR_2") (pintype "input"))
    )
    (net (code "135") (name "VLCD") (class "Default")
      (node (ref "C200") (pin "2") (pinfunction "2_2") (pintype "passive"))
      (node (ref "C207") (pin "2") (pinfunction "2_2") (pintype "passive"))
      (node (ref "C213") (pin "2") (pinfunction "2_2") (pintype "passive"))
      (node (ref "C218") (pin "2") (pinfunction "2_2") (pintype "passive"))
      (node (ref "C220") (pin "2") (pinfunction "2_2") (pintype "passive"))
      (node (ref "C223") (pin "1") (pinfunction "1_1") (pintype "passive"))
      (node (ref "H200") (pin "28") (pinfunction "28_28") (pintype "passive"))
      (node (ref "L200") (pin "2") (pinfunction "2_2") (pintype "passive"))
      (node (ref "L206") (pin "1") (pinfunction "1_1") (pintype "passive"))
      (node (ref "U200") (pin "23") (pinfunction "VCCB_23") (pintype "power_in"))
      (node (ref "U200") (pin "24") (pinfunction "VCCB_24") (pintype "power_in"))
      (node (ref "U203") (pin "23") (pinfunction "VCCB_23") (pintype "power_in"))
      (node (ref "U203") (pin "24") (pinfunction "VCCB_24") (pintype "power_in"))
      (node (ref "U205") (pin "23") (pinfunction "VCCB_23") (pintype "power_in"))
      (node (ref "U205") (pin "24") (pinfunction "VCCB_24") (pintype "power_in"))
      (node (ref "U207") (pin "23") (pinfunction "VCCB_23") (pintype "power_in"))
      (node (ref "U207") (pin "24") (pinfunction "VCCB_24") (pintype "power_in"))
    )
    (net (code "136") (name "VSB") (class "Default")
      (node (ref "C226") (pin "2") (pinfunction "2_2") (pintype "passive"))
      (node (ref "R211") (pin "1") (pinfunction "1_1") (pintype "passive"))
      (node (ref "R213") (pin "2") (pinfunction "2_2") (pintype "passive"))
      (node (ref "R215") (pin "1") (pinfunction "1_1") (pintype "passive"))
      (node (ref "T203") (pin "1") (pinfunction "G_1") (pintype "passive"))
    )
    (net (code "137") (name "VVGA") (class "Default")
      (node (ref "C201") (pin "2") (pinfunction "2_2") (pintype "passive"))
      (node (ref "C202") (pin "2") (pinfunction "2_2") (pintype "passive"))
      (node (ref "C203") (pin "2") (pinfunction "2_2") (pintype "passive"))
      (node (ref "C204") (pin "2") (pinfunction "2_2") (pintype "passive"))
      (node (ref "C205") (pin "2") (pinfunction "2_2") (pintype "passive"))
      (node (ref "L200") (pin "1") (pinfunction "1_1") (pintype "passive"))
      (node (ref "L202") (pin "1") (pinfunction "1_1") (pintype "passive"))
      (node (ref "U201") (pin "13") (pinfunction "VAA_13") (pintype "power_in"))
      (node (ref "U201") (pin "29") (pinfunction "VAA_29") (pintype "power_in"))
      (node (ref "U201") (pin "30") (pinfunction "VAA_30") (pintype "power_in"))
    )
    (net (code "138") (name "unconnected-(U208-IREDC-Pad2)") (class "Default")
      (node (ref "U208") (pin "2") (pinfunction "IREDC_2") (pintype "passive+no_connect"))
    )
    (net (code "139") (name "unconnected-(U208-NC-Pad7)") (class "Default")
      (node (ref "U208") (pin "7") (pinfunction "NC_7") (pintype "passive+no_connect"))
    )
  )
)
